# 4-POWER.net
KiCad netlist of a schematic drawn in Altium Designer
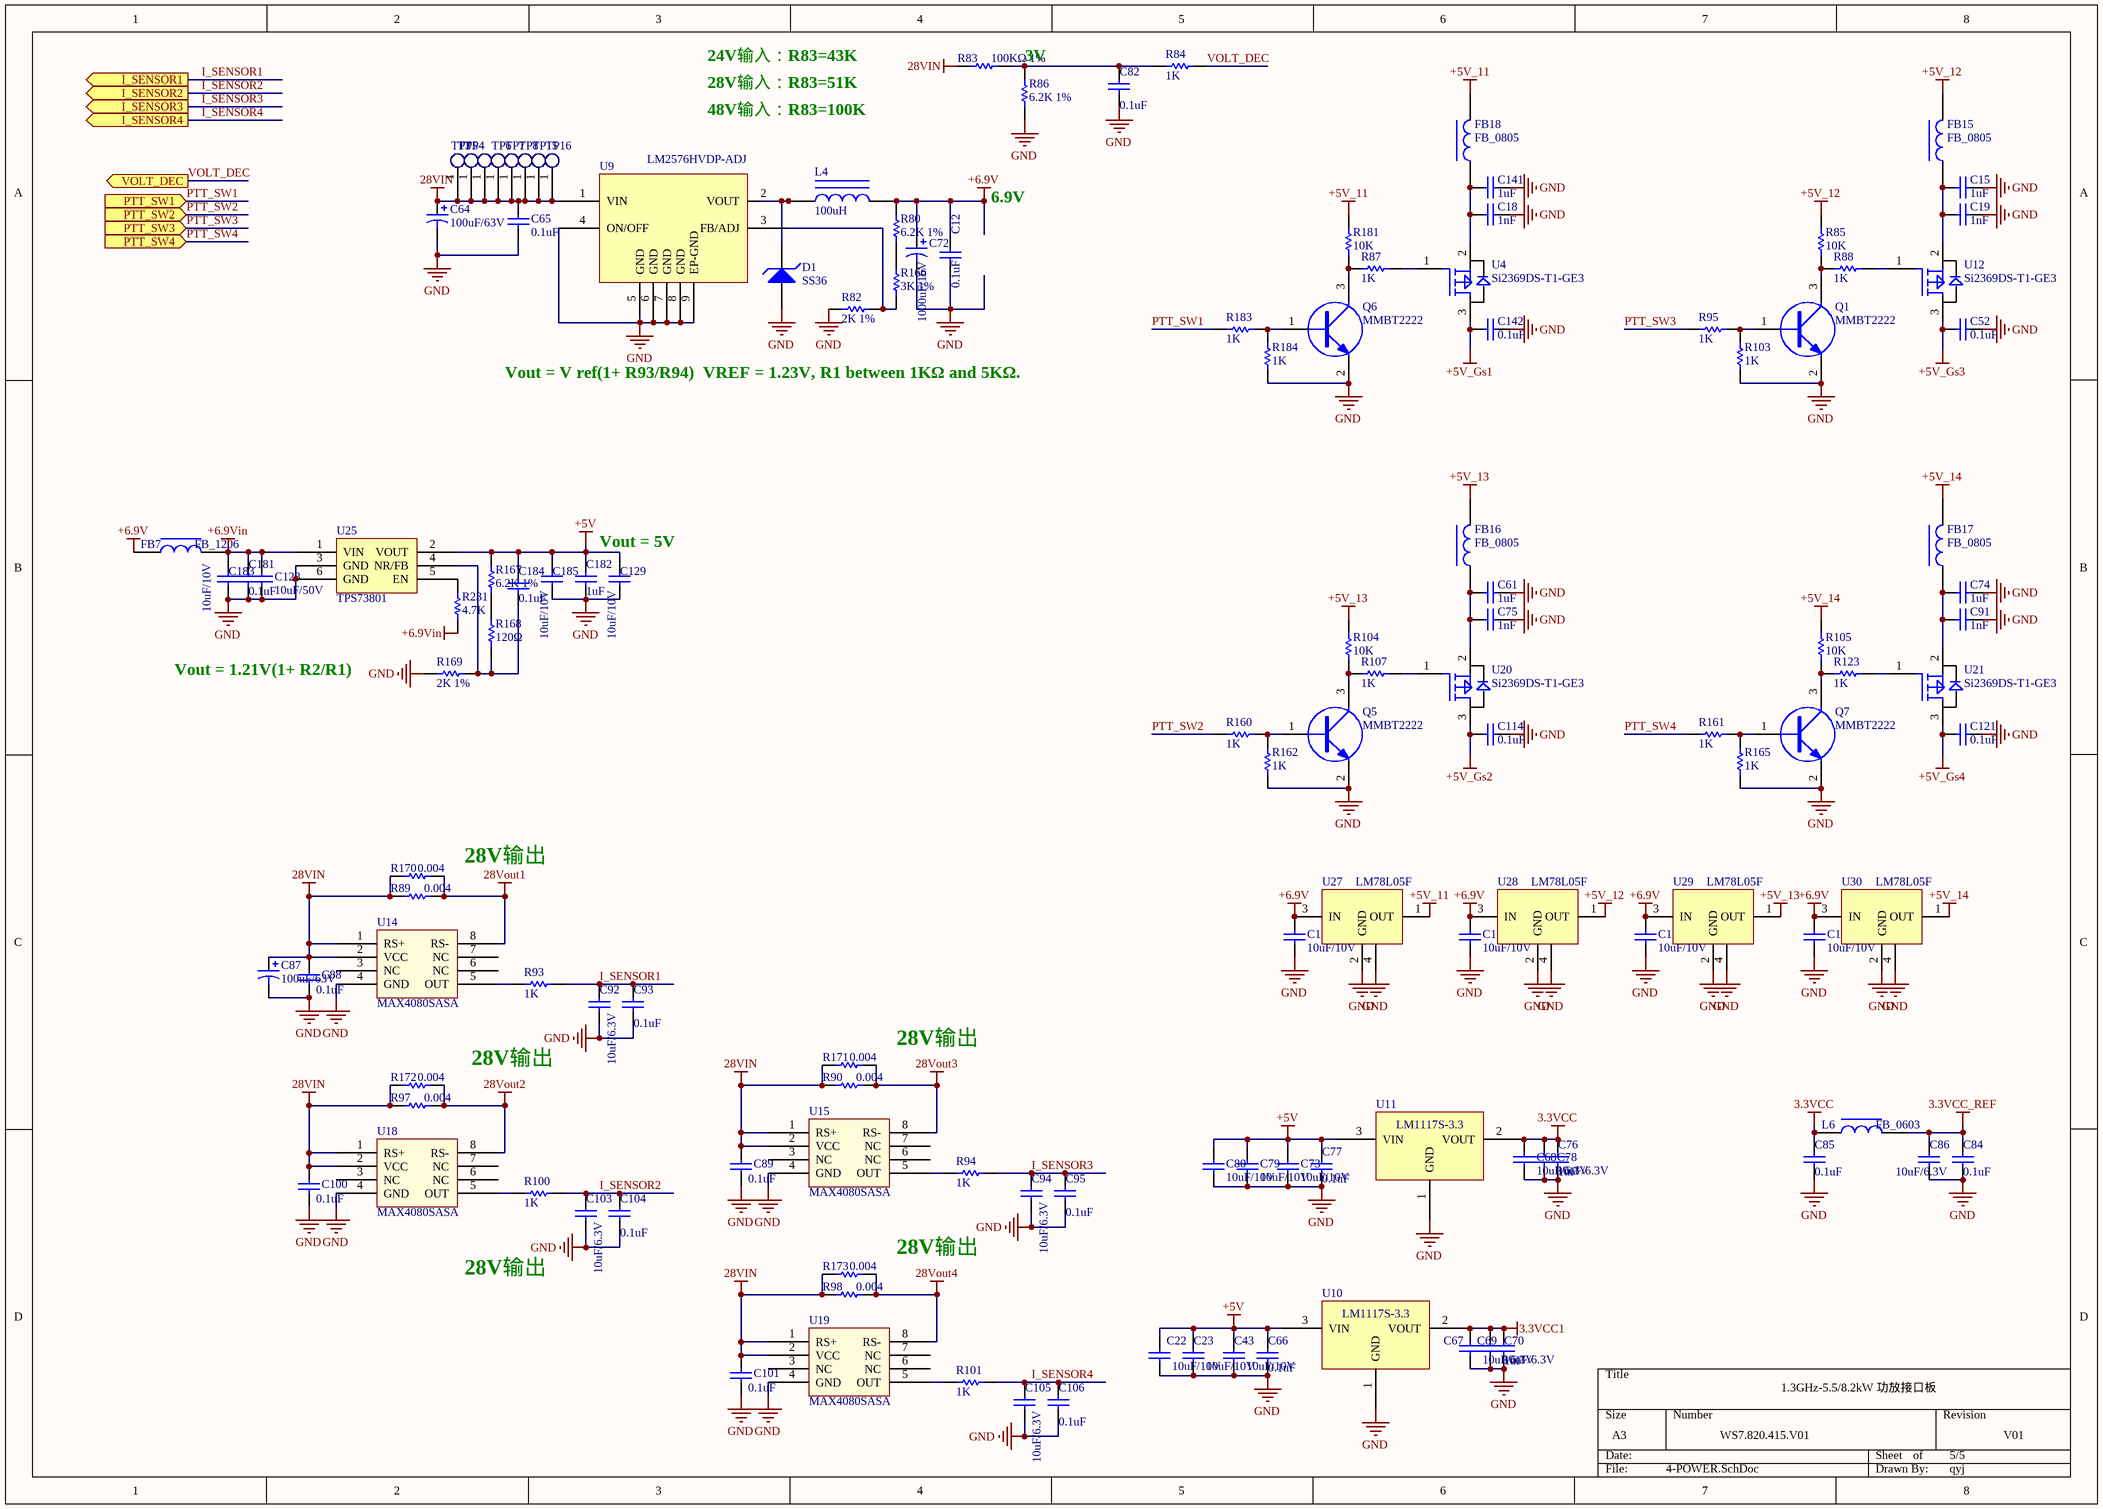
[diagram p0: 4-POWER.SchDoc]

(export (version "E")
  (design (tool "Eeschema 10.0.6"))
  (components
    (comp (ref "C12")
      (value "0.1uF")
      (footprint "C0603")
      (description "贴片电容_GRM188R71H104KA01D_0.1uF±10%,50V,0603")
      (libsource (lib "20贴片电容0603") (part "0.1uF贴片电容"))
    )
    (comp (ref "C15")
      (value "1uF")
      (footprint "C0603")
      (description "贴片电容_GRM188R61A105KA61D_1uF±10%,10V,0603")
      (libsource (lib "20贴片电容0603") (part "1uF贴片电容"))
    )
    (comp (ref "C18")
      (value "1nF")
      (footprint "C0603")
      (description "贴片电容_GRM188R71H102KA01_1000pF±10%,50V,0603")
      (libsource (lib "20贴片电容0603") (part "1000pF贴片电容"))
    )
    (comp (ref "C19")
      (value "1nF")
      (footprint "C0603")
      (description "贴片电容_GRM188R71H102KA01_1000pF±10%,50V,0603")
      (libsource (lib "20贴片电容0603") (part "1000pF贴片电容"))
    )
    (comp (ref "C22")
      (value "10uF/10V")
      (footprint "C0805")
      (description "贴片电容_GRM21BR61A106KE19L_10uF±10%,10V,0805")
      (libsource (lib "21贴片电容0805") (part "10uF贴片电容"))
    )
    (comp (ref "C23")
      (value "10uF/10V")
      (footprint "C0805")
      (description "贴片电容_GRM21BR61A106KE19L_10uF±10%,10V,0805")
      (libsource (lib "21贴片电容0805") (part "10uF贴片电容"))
    )
    (comp (ref "C43")
      (value "10uF/10V")
      (footprint "C0805")
      (description "贴片电容_GRM21BR61A106KE19L_10uF±10%,10V,0805")
      (libsource (lib "21贴片电容0805") (part "10uF贴片电容"))
    )
    (comp (ref "C52")
      (value "0.1uF")
      (footprint "C0603")
      (description "贴片电容_GRM188R71H104KA01D_0.1uF±10%,50V,0603")
      (libsource (lib "20贴片电容0603") (part "0.1uF贴片电容"))
    )
    (comp (ref "C61")
      (value "1uF")
      (footprint "C0603")
      (description "贴片电容_GRM188R61A105KA61D_1uF±10%,10V,0603")
      (libsource (lib "20贴片电容0603") (part "1uF贴片电容"))
    )
    (comp (ref "C64")
      (value "100uF/63V")
      (footprint "ECAP2SM_10R4x10R4")
      (description "贴片电解电容_VEJ101M1JTR-1010_100uF/63V,±20%,表贴D10*H10")
      (libsource (lib "24电解电容") (part "100uF/63V"))
    )
    (comp (ref "C65")
      (value "0.1uF")
      (footprint "C0603")
      (description "贴片电容_GRM188R71H104KA01D_0.1uF±10%,50V,0603")
      (libsource (lib "20贴片电容0603") (part "0.1uF贴片电容"))
    )
    (comp (ref "C66")
      (value "0.1uF")
      (footprint "C0603")
      (description "贴片电容_GRM188R71H104KA01D_0.1uF±10%,50V,0603")
      (libsource (lib "20贴片电容0603") (part "0.1uF贴片电容"))
    )
    (comp (ref "C67")
      (value "10uF/6.3V")
      (footprint "C0603")
      (description "贴片电容_GRM188R60J106ME47D_10uF±20%,6.3V,0603")
      (libsource (lib "20贴片电容0603") (part "10uF贴片电容"))
    )
    (comp (ref "C68")
      (value "10uF/6.3V")
      (footprint "C0603")
      (description "贴片电容_GRM188R60J106ME47D_10uF±20%,6.3V,0603")
      (libsource (lib "20贴片电容0603") (part "10uF贴片电容"))
    )
    (comp (ref "C69")
      (value "10uF/6.3V")
      (footprint "C0603")
      (description "贴片电容_GRM188R60J106ME47D_10uF±20%,6.3V,0603")
      (libsource (lib "20贴片电容0603") (part "10uF贴片电容"))
    )
    (comp (ref "C70")
      (value "1uF")
      (footprint "C0603")
      (description "贴片电容_GRM188R61A105KA61D_1uF±10%,10V,0603")
      (libsource (lib "20贴片电容0603") (part "1uF贴片电容"))
    )
    (comp (ref "C72")
      (value "1000uF/16V")
      (footprint "ECAP2SM_10R4x10R4")
      (description "贴片电解电容_VE102M1CTR-1010_1000uF/16V,±20%,表贴10*10")
      (libsource (lib "24电解电容") (part "1000uF/16V"))
    )
    (comp (ref "C73")
      (value "10uF/10V")
      (footprint "C0805")
      (description "贴片电容_GRM21BR61A106KE19L_10uF±10%,10V,0805")
      (libsource (lib "21贴片电容0805") (part "10uF贴片电容"))
    )
    (comp (ref "C74")
      (value "1uF")
      (footprint "C0603")
      (description "贴片电容_GRM188R61A105KA61D_1uF±10%,10V,0603")
      (libsource (lib "20贴片电容0603") (part "1uF贴片电容"))
    )
    (comp (ref "C75")
      (value "1nF")
      (footprint "C0603")
      (description "贴片电容_GRM188R71H102KA01_1000pF±10%,50V,0603")
      (libsource (lib "20贴片电容0603") (part "1000pF贴片电容"))
    )
    (comp (ref "C76")
      (value "1uF")
      (footprint "C0603")
      (description "贴片电容_GRM188R61A105KA61D_1uF±10%,10V,0603")
      (libsource (lib "20贴片电容0603") (part "1uF贴片电容"))
    )
    (comp (ref "C77")
      (value "0.1uF")
      (footprint "C0603")
      (description "贴片电容_GRM188R71H104KA01D_0.1uF±10%,50V,0603")
      (libsource (lib "20贴片电容0603") (part "0.1uF贴片电容"))
    )
    (comp (ref "C78")
      (value "10uF/6.3V")
      (footprint "C0603")
      (description "贴片电容_GRM188R60J106ME47D_10uF±20%,6.3V,0603")
      (libsource (lib "20贴片电容0603") (part "10uF贴片电容"))
    )
    (comp (ref "C79")
      (value "10uF/10V")
      (footprint "C0805")
      (description "贴片电容_GRM21BR61A106KE19L_10uF±10%,10V,0805")
      (libsource (lib "21贴片电容0805") (part "10uF贴片电容"))
    )
    (comp (ref "C80")
      (value "10uF/10V")
      (footprint "C0805")
      (description "贴片电容_GRM21BR61A106KE19L_10uF±10%,10V,0805")
      (libsource (lib "21贴片电容0805") (part "10uF贴片电容"))
    )
    (comp (ref "C82")
      (value "0.1uF")
      (footprint "C0603")
      (description "贴片电容_GRM188R71H104KA01D_0.1uF±10%,50V,0603")
      (libsource (lib "20贴片电容0603") (part "0.1uF贴片电容"))
    )
    (comp (ref "C84")
      (value "0.1uF")
      (footprint "C0603")
      (description "贴片电容_GRM188R71H104KA01D_0.1uF±10%,50V,0603")
      (libsource (lib "20贴片电容0603") (part "0.1uF贴片电容"))
    )
    (comp (ref "C85")
      (value "0.1uF")
      (footprint "C0603")
      (description "贴片电容_GRM188R71H104KA01D_0.1uF±10%,50V,0603")
      (libsource (lib "20贴片电容0603") (part "0.1uF贴片电容"))
    )
    (comp (ref "C86")
      (value "10uF/6.3V")
      (footprint "C0603")
      (description "贴片电容_GRM188R60J106ME47D_10uF±20%,6.3V,0603")
      (libsource (lib "20贴片电容0603") (part "10uF贴片电容"))
    )
    (comp (ref "C87")
      (value "100uF/63V")
      (footprint "ECAP2SM_10R4x10R4")
      (description "贴片电解电容_VEJ101M1JTR-1010_100uF/63V,±20%,表贴D10*H10")
      (libsource (lib "24电解电容") (part "100uF/63V"))
    )
    (comp (ref "C88")
      (value "0.1uF")
      (footprint "C0603")
      (description "贴片电容_GRM188R71H104KA01D_0.1uF±10%,50V,0603")
      (libsource (lib "20贴片电容0603") (part "0.1uF贴片电容"))
    )
    (comp (ref "C89")
      (value "0.1uF")
      (footprint "C0603")
      (description "贴片电容_GRM188R71H104KA01D_0.1uF±10%,50V,0603")
      (libsource (lib "20贴片电容0603") (part "0.1uF贴片电容"))
    )
    (comp (ref "C91")
      (value "1nF")
      (footprint "C0603")
      (description "贴片电容_GRM188R71H102KA01_1000pF±10%,50V,0603")
      (libsource (lib "20贴片电容0603") (part "1000pF贴片电容"))
    )
    (comp (ref "C92")
      (value "10uF/6.3V")
      (footprint "C0603")
      (description "贴片电容_GRM188R60J106ME47D_10uF±20%,6.3V,0603")
      (libsource (lib "20贴片电容0603") (part "10uF贴片电容"))
    )
    (comp (ref "C93")
      (value "0.1uF")
      (footprint "C0603")
      (description "贴片电容_GRM188R71H104KA01D_0.1uF±10%,50V,0603")
      (libsource (lib "20贴片电容0603") (part "0.1uF贴片电容"))
    )
    (comp (ref "C94")
      (value "10uF/6.3V")
      (footprint "C0603")
      (description "贴片电容_GRM188R60J106ME47D_10uF±20%,6.3V,0603")
      (libsource (lib "20贴片电容0603") (part "10uF贴片电容"))
    )
    (comp (ref "C95")
      (value "0.1uF")
      (footprint "C0603")
      (description "贴片电容_GRM188R71H104KA01D_0.1uF±10%,50V,0603")
      (libsource (lib "20贴片电容0603") (part "0.1uF贴片电容"))
    )
    (comp (ref "C100")
      (value "0.1uF")
      (footprint "C0603")
      (description "贴片电容_GRM188R71H104KA01D_0.1uF±10%,50V,0603")
      (libsource (lib "20贴片电容0603") (part "0.1uF贴片电容"))
    )
    (comp (ref "C101")
      (value "0.1uF")
      (footprint "C0603")
      (description "贴片电容_GRM188R71H104KA01D_0.1uF±10%,50V,0603")
      (libsource (lib "20贴片电容0603") (part "0.1uF贴片电容"))
    )
    (comp (ref "C103")
      (value "10uF/6.3V")
      (footprint "C0603")
      (description "贴片电容_GRM188R60J106ME47D_10uF±20%,6.3V,0603")
      (libsource (lib "20贴片电容0603") (part "10uF贴片电容"))
    )
    (comp (ref "C104")
      (value "0.1uF")
      (footprint "C0603")
      (description "贴片电容_GRM188R71H104KA01D_0.1uF±10%,50V,0603")
      (libsource (lib "20贴片电容0603") (part "0.1uF贴片电容"))
    )
    (comp (ref "C105")
      (value "10uF/6.3V")
      (footprint "C0603")
      (description "贴片电容_GRM188R60J106ME47D_10uF±20%,6.3V,0603")
      (libsource (lib "20贴片电容0603") (part "10uF贴片电容"))
    )
    (comp (ref "C106")
      (value "0.1uF")
      (footprint "C0603")
      (description "贴片电容_GRM188R71H104KA01D_0.1uF±10%,50V,0603")
      (libsource (lib "20贴片电容0603") (part "0.1uF贴片电容"))
    )
    (comp (ref "C114")
      (value "0.1uF")
      (footprint "C0603")
      (description "贴片电容_GRM188R71H104KA01D_0.1uF±10%,50V,0603")
      (libsource (lib "20贴片电容0603") (part "0.1uF贴片电容"))
    )
    (comp (ref "C121")
      (value "0.1uF")
      (footprint "C0603")
      (description "贴片电容_GRM188R71H104KA01D_0.1uF±10%,50V,0603")
      (libsource (lib "20贴片电容0603") (part "0.1uF贴片电容"))
    )
    (comp (ref "C128")
      (value "10uF/50V")
      (footprint "C1210")
      (description "贴片电容_GRM32ER71H106KA12L_10uF±10%,50V,1210")
      (libsource (lib "23贴片电容1210") (part "10uF贴片电容"))
    )
    (comp (ref "C129")
      (value "10uF/10V")
      (footprint "C0805")
      (description "贴片电容_GRM21BR61A106KE19L_10uF±10%,10V,0805")
      (libsource (lib "21贴片电容0805") (part "10uF贴片电容"))
    )
    (comp (ref "C132")
      (value "10uF/10V")
      (footprint "C0805")
      (description "贴片电容_GRM21BR61A106KE19L_10uF±10%,10V,0805")
      (libsource (lib "21贴片电容0805") (part "10uF贴片电容"))
    )
    (comp (ref "C133")
      (value "10uF/10V")
      (footprint "C0805")
      (description "贴片电容_GRM21BR61A106KE19L_10uF±10%,10V,0805")
      (libsource (lib "21贴片电容0805") (part "10uF贴片电容"))
    )
    (comp (ref "C134")
      (value "10uF/10V")
      (footprint "C0805")
      (description "贴片电容_GRM21BR61A106KE19L_10uF±10%,10V,0805")
      (libsource (lib "21贴片电容0805") (part "10uF贴片电容"))
    )
    (comp (ref "C135")
      (value "10uF/10V")
      (footprint "C0805")
      (description "贴片电容_GRM21BR61A106KE19L_10uF±10%,10V,0805")
      (libsource (lib "21贴片电容0805") (part "10uF贴片电容"))
    )
    (comp (ref "C141")
      (value "1uF")
      (footprint "C0603")
      (description "贴片电容_GRM188R61A105KA61D_1uF±10%,10V,0603")
      (libsource (lib "20贴片电容0603") (part "1uF贴片电容"))
    )
    (comp (ref "C142")
      (value "0.1uF")
      (footprint "C0603")
      (description "贴片电容_GRM188R71H104KA01D_0.1uF±10%,50V,0603")
      (libsource (lib "20贴片电容0603") (part "0.1uF贴片电容"))
    )
    (comp (ref "C181")
      (value "0.1uF")
      (footprint "C0603")
      (description "贴片电容_GRM188R71H104KA01D_0.1uF±10%,50V,0603")
      (libsource (lib "20贴片电容0603") (part "0.1uF贴片电容"))
    )
    (comp (ref "C182")
      (value "1uF")
      (footprint "C0603")
      (description "贴片电容_GRM188R61A105KA61D_1uF±10%,10V,0603")
      (libsource (lib "20贴片电容0603") (part "1uF贴片电容"))
    )
    (comp (ref "C183")
      (value "10uF/10V")
      (footprint "C0805")
      (description "贴片电容_GRM21BR61A106KE19L_10uF±10%,10V,0805")
      (libsource (lib "21贴片电容0805") (part "10uF贴片电容"))
    )
    (comp (ref "C184")
      (value "0.1uF")
      (footprint "C0603")
      (description "贴片电容_GRM188R71H104KA01D_0.1uF±10%,50V,0603")
      (libsource (lib "20贴片电容0603") (part "0.1uF贴片电容"))
    )
    (comp (ref "C185")
      (value "10uF/10V")
      (footprint "C0805")
      (description "贴片电容_GRM21BR61A106KE19L_10uF±10%,10V,0805")
      (libsource (lib "21贴片电容0805") (part "10uF贴片电容"))
    )
    (comp (ref "D1")
      (value "SS36")
      (footprint "DO-214AC")
      (description "肖特基整流二极管_SS36_封装SMA,3A/60V")
      (libsource (lib "40二极管") (part "肖特基整流二极管_SS36"))
    )
    (comp (ref "FB7")
      (value "FB_1206")
      (footprint "L1206")
      (description "贴片磁珠_30R,6A,1206")
      (libsource (lib "34贴片磁珠1206") (part "1206贴片磁珠"))
    )
    (comp (ref "FB15")
      (value "FB_0805")
      (footprint "L0805")
      (description "贴片磁珠_600R,0805")
      (libsource (lib "33贴片磁珠0805") (part "0805贴片磁珠"))
    )
    (comp (ref "FB16")
      (value "FB_0805")
      (footprint "L0805")
      (description "贴片磁珠_600R,0805")
      (libsource (lib "33贴片磁珠0805") (part "0805贴片磁珠"))
    )
    (comp (ref "FB17")
      (value "FB_0805")
      (footprint "L0805")
      (description "贴片磁珠_600R,0805")
      (libsource (lib "33贴片磁珠0805") (part "0805贴片磁珠"))
    )
    (comp (ref "FB18")
      (value "FB_0805")
      (footprint "L0805")
      (description "贴片磁珠_600R,0805")
      (libsource (lib "33贴片磁珠0805") (part "0805贴片磁珠"))
    )
    (comp (ref "L4")
      (value "100uH")
      (footprint "PL2SM-12R5x12R5")
      (description "贴片功率电感_SLF12575T-101M1R9-PF_100uH±20%,额定电流1.9A,12.5x12.5")
      (libsource (lib "32贴片功率电感") (part "100uH贴片功率电感"))
    )
    (comp (ref "L6")
      (value "FB_0603")
      (footprint "L0603")
      (description "贴片磁珠_100R,0603")
      (libsource (lib "32贴片磁珠0603") (part "0603贴片磁珠"))
    )
    (comp (ref "Q1")
      (value "MMBT2222")
      (footprint "SOT23-3")
      (description "NPN三极管_MMBT2222_表贴SOT23")
      (libsource (lib "50三极管") (part "MMBT2222"))
    )
    (comp (ref "Q5")
      (value "MMBT2222")
      (footprint "SOT23-3")
      (description "NPN三极管_MMBT2222_表贴SOT23")
      (libsource (lib "50三极管") (part "MMBT2222"))
    )
    (comp (ref "Q6")
      (value "MMBT2222")
      (footprint "SOT23-3")
      (description "NPN三极管_MMBT2222_表贴SOT23")
      (libsource (lib "50三极管") (part "MMBT2222"))
    )
    (comp (ref "Q7")
      (value "MMBT2222")
      (footprint "SOT23-3")
      (description "NPN三极管_MMBT2222_表贴SOT23")
      (libsource (lib "50三极管") (part "MMBT2222"))
    )
    (comp (ref "R80")
      (value "6.2K 1%")
      (footprint "R0603")
      (description "贴片电阻_6.2K±5%,0603")
      (libsource (lib "10贴片电阻0603") (part "6.2K贴片电阻"))
    )
    (comp (ref "R82")
      (value "2K 1%")
      (footprint "R0603")
      (description "贴片电阻_2K±5%,0603")
      (libsource (lib "10贴片电阻0603") (part "2K贴片电阻"))
    )
    (comp (ref "R83")
      (value "100KΩ 1%")
      (footprint "R0603")
      (description "贴片电阻_12.4K±1%,0603")
      (libsource (lib "10贴片电阻0603") (part "12.4K贴片电阻"))
    )
    (comp (ref "R84")
      (value "1K")
      (footprint "R0603")
      (description "贴片电阻_1K±5%,0603")
      (libsource (lib "10贴片电阻0603") (part "1K贴片电阻"))
    )
    (comp (ref "R85")
      (value "10K")
      (footprint "R0603")
      (description "贴片电阻_10K±5%,0603")
      (libsource (lib "10贴片电阻0603") (part "10K贴片电阻"))
    )
    (comp (ref "R86")
      (value "6.2K 1%")
      (footprint "R0603")
      (description "贴片电阻_1.5K±5%,0603")
      (libsource (lib "10贴片电阻0603") (part "1.5K贴片电阻"))
    )
    (comp (ref "R87")
      (value "1K")
      (footprint "R0603")
      (description "贴片电阻_1K±5%,0603")
      (libsource (lib "10贴片电阻0603") (part "1K贴片电阻"))
    )
    (comp (ref "R88")
      (value "1K")
      (footprint "R0603")
      (description "贴片电阻_1K±5%,0603")
      (libsource (lib "10贴片电阻0603") (part "1K贴片电阻"))
    )
    (comp (ref "R89")
      (value "0.004")
      (footprint "R2512")
      (description "贴片电阻_LR12DTDSR004_0.004±5%,2W,2512")
      (libsource (lib "15贴片检流电阻") (part "0.004Ω检流电阻-标准封装"))
    )
    (comp (ref "R90")
      (value "0.004")
      (footprint "R2512")
      (description "贴片电阻_LR12DTDSR004_0.004±5%,2W,2512")
      (libsource (lib "15贴片检流电阻") (part "0.004Ω检流电阻-标准封装"))
    )
    (comp (ref "R93")
      (value "1K")
      (footprint "R0603")
      (description "贴片电阻_1K±5%,0603")
      (libsource (lib "10贴片电阻0603") (part "1K贴片电阻"))
    )
    (comp (ref "R94")
      (value "1K")
      (footprint "R0603")
      (description "贴片电阻_1K±5%,0603")
      (libsource (lib "10贴片电阻0603") (part "1K贴片电阻"))
    )
    (comp (ref "R95")
      (value "1K")
      (footprint "R0603")
      (description "贴片电阻_1K±5%,0603")
      (libsource (lib "10贴片电阻0603") (part "1K贴片电阻"))
    )
    (comp (ref "R97")
      (value "0.004")
      (footprint "R2512")
      (description "贴片电阻_LR12DTDSR004_0.004±5%,2W,2512")
      (libsource (lib "15贴片检流电阻") (part "0.004Ω检流电阻-标准封装"))
    )
    (comp (ref "R98")
      (value "0.004")
      (footprint "R2512")
      (description "贴片电阻_LR12DTDSR004_0.004±5%,2W,2512")
      (libsource (lib "15贴片检流电阻") (part "0.004Ω检流电阻-标准封装"))
    )
    (comp (ref "R100")
      (value "1K")
      (footprint "R0603")
      (description "贴片电阻_1K±5%,0603")
      (libsource (lib "10贴片电阻0603") (part "1K贴片电阻"))
    )
    (comp (ref "R101")
      (value "1K")
      (footprint "R0603")
      (description "贴片电阻_1K±5%,0603")
      (libsource (lib "10贴片电阻0603") (part "1K贴片电阻"))
    )
    (comp (ref "R103")
      (value "1K")
      (footprint "R0603")
      (description "贴片电阻_1K±5%,0603")
      (libsource (lib "10贴片电阻0603") (part "1K贴片电阻"))
    )
    (comp (ref "R104")
      (value "10K")
      (footprint "R0603")
      (description "贴片电阻_10K±5%,0603")
      (libsource (lib "10贴片电阻0603") (part "10K贴片电阻"))
    )
    (comp (ref "R105")
      (value "10K")
      (footprint "R0603")
      (description "贴片电阻_10K±5%,0603")
      (libsource (lib "10贴片电阻0603") (part "10K贴片电阻"))
    )
    (comp (ref "R107")
      (value "1K")
      (footprint "R0603")
      (description "贴片电阻_1K±5%,0603")
      (libsource (lib "10贴片电阻0603") (part "1K贴片电阻"))
    )
    (comp (ref "R123")
      (value "1K")
      (footprint "R0603")
      (description "贴片电阻_1K±5%,0603")
      (libsource (lib "10贴片电阻0603") (part "1K贴片电阻"))
    )
    (comp (ref "R160")
      (value "1K")
      (footprint "R0603")
      (description "贴片电阻_1K±5%,0603")
      (libsource (lib "10贴片电阻0603") (part "1K贴片电阻"))
    )
    (comp (ref "R161")
      (value "1K")
      (footprint "R0603")
      (description "贴片电阻_1K±5%,0603")
      (libsource (lib "10贴片电阻0603") (part "1K贴片电阻"))
    )
    (comp (ref "R162")
      (value "1K")
      (footprint "R0603")
      (description "贴片电阻_1K±5%,0603")
      (libsource (lib "10贴片电阻0603") (part "1K贴片电阻"))
    )
    (comp (ref "R165")
      (value "1K")
      (footprint "R0603")
      (description "贴片电阻_1K±5%,0603")
      (libsource (lib "10贴片电阻0603") (part "1K贴片电阻"))
    )
    (comp (ref "R166")
      (value "3K 1%")
      (footprint "R0603")
      (description "贴片电阻_3K±5%,0603")
      (libsource (lib "10贴片电阻0603") (part "3K贴片电阻"))
    )
    (comp (ref "R167")
      (value "6.2K 1%")
      (footprint "R0603")
      (description "贴片电阻_6.2K±5%,0603")
      (libsource (lib "10贴片电阻0603") (part "6.2K贴片电阻"))
    )
    (comp (ref "R168")
      (value "120Ω")
      (footprint "R0603")
      (description "贴片电阻_120Ω±5%,0603")
      (libsource (lib "10贴片电阻0603") (part "120Ω贴片电阻"))
    )
    (comp (ref "R169")
      (value "2K 1%")
      (footprint "R0603")
      (description "贴片电阻_2K±5%,0603")
      (libsource (lib "10贴片电阻0603") (part "2K贴片电阻"))
    )
    (comp (ref "R170")
      (value "0.004")
      (footprint "R2512")
      (description "贴片电阻_LR12DTDSR004_0.004±5%,2W,2512")
      (libsource (lib "15贴片检流电阻") (part "0.004Ω检流电阻-标准封装"))
    )
    (comp (ref "R171")
      (value "0.004")
      (footprint "R2512")
      (description "贴片电阻_LR12DTDSR004_0.004±5%,2W,2512")
      (libsource (lib "15贴片检流电阻") (part "0.004Ω检流电阻-标准封装"))
    )
    (comp (ref "R172")
      (value "0.004")
      (footprint "R2512")
      (description "贴片电阻_LR12DTDSR004_0.004±5%,2W,2512")
      (libsource (lib "15贴片检流电阻") (part "0.004Ω检流电阻-标准封装"))
    )
    (comp (ref "R173")
      (value "0.004")
      (footprint "R2512")
      (description "贴片电阻_LR12DTDSR004_0.004±5%,2W,2512")
      (libsource (lib "15贴片检流电阻") (part "0.004Ω检流电阻-标准封装"))
    )
    (comp (ref "R181")
      (value "10K")
      (footprint "R0603")
      (description "贴片电阻_10K±5%,0603")
      (libsource (lib "10贴片电阻0603") (part "10K贴片电阻"))
    )
    (comp (ref "R183")
      (value "1K")
      (footprint "R0603")
      (description "贴片电阻_1K±5%,0603")
      (libsource (lib "10贴片电阻0603") (part "1K贴片电阻"))
    )
    (comp (ref "R184")
      (value "1K")
      (footprint "R0603")
      (description "贴片电阻_1K±5%,0603")
      (libsource (lib "10贴片电阻0603") (part "1K贴片电阻"))
    )
    (comp (ref "R231")
      (value "4.7K")
      (footprint "R0603")
      (description "贴片电阻_4.7K±5%,0603")
      (libsource (lib "10贴片电阻0603") (part "4.7K贴片电阻"))
    )
    (comp (ref "TP3")
      (value "RTF-76-006-M4-S")
      (footprint "FC-M4")
      (description "表贴测试点1mm")
      (libsource (lib "92-其他（穿心电容，test等）") (part "TP2mm"))
    )
    (comp (ref "TP4")
      (value "RTF-76-006-M4-S")
      (footprint "FC-M4")
      (description "表贴测试点1mm")
      (libsource (lib "92-其他（穿心电容，test等）") (part "TP2mm"))
    )
    (comp (ref "TP5")
      (value "RTF-76-006-M4-S")
      (footprint "FC-M4")
      (description "表贴测试点1mm")
      (libsource (lib "92-其他（穿心电容，test等）") (part "TP2mm"))
    )
    (comp (ref "TP6")
      (value "RTF-76-006-M4-S")
      (footprint "FC-M4")
      (description "表贴测试点1mm")
      (libsource (lib "92-其他（穿心电容，test等）") (part "TP2mm"))
    )
    (comp (ref "TP7")
      (value "RTF-76-006-M4-S")
      (footprint "FC-M4")
      (description "表贴测试点1mm")
      (libsource (lib "92-其他（穿心电容，test等）") (part "TP2mm"))
    )
    (comp (ref "TP8")
      (value "RTF-76-006-M4-S")
      (footprint "FC-M4")
      (description "表贴测试点1mm")
      (libsource (lib "92-其他（穿心电容，test等）") (part "TP2mm"))
    )
    (comp (ref "TP15")
      (value "RTF-76-006-M4-S")
      (footprint "FC-M4")
      (description "表贴测试点1mm")
      (libsource (lib "92-其他（穿心电容，test等）") (part "TP2mm"))
    )
    (comp (ref "TP16")
      (value "RTF-76-006-M4-S")
      (footprint "FC-M4")
      (description "表贴测试点1mm")
      (libsource (lib "92-其他（穿心电容，test等）") (part "TP2mm"))
    )
    (comp (ref "U4")
      (value "Si2369DS-T1-GE3")
      (footprint "SOT23-3")
      (description "P-MOS_Si2369DS-T1-GE3_SOT23")
      (libsource (lib "51场效应管") (part "Si2369DS-T1-GE3"))
    )
    (comp (ref "U9")
      (value "LM2576HVDP-ADJ")
      (footprint "SOIC8_1R27_3R9x4R9-1")
      (description "稳压集成电路_LM2576HVDP-ADJ_3A输出,SOIC8")
      (libsource (lib "78电源芯片") (part "LM2576HVDP-ADJ"))
    )
    (comp (ref "U10")
      (value "LM1117S-3.3")
      (footprint "SOT-223")
      (description "LDO_LM1117S-3.3_1A输出,SOT223")
      (libsource (lib "78电源芯片") (part "LM1117S-3.3"))
    )
    (comp (ref "U11")
      (value "LM1117S-3.3")
      (footprint "SOT-223")
      (description "LDO_LM1117S-3.3_1A输出,SOT223")
      (libsource (lib "78电源芯片") (part "LM1117S-3.3"))
    )
    (comp (ref "U12")
      (value "Si2369DS-T1-GE3")
      (footprint "SOT23-3")
      (description "P-MOS_Si2369DS-T1-GE3_SOT23")
      (libsource (lib "51场效应管") (part "Si2369DS-T1-GE3"))
    )
    (comp (ref "U14")
      (value "MAX4080SASA")
      (footprint "SOIC8_1R27_3R9x4R9")
      (description "电流检测放大器_MAX4080SASA_SOIC8")
      (libsource (lib "79电流检测芯片") (part "MAX4080TASA"))
    )
    (comp (ref "U15")
      (value "MAX4080SASA")
      (footprint "SOIC8_1R27_3R9x4R9")
      (description "电流检测放大器_MAX4080SASA_SOIC8")
      (libsource (lib "79电流检测芯片") (part "MAX4080TASA"))
    )
    (comp (ref "U18")
      (value "MAX4080SASA")
      (footprint "SOIC8_1R27_3R9x4R9")
      (description "电流检测放大器_MAX4080SASA_SOIC8")
      (libsource (lib "79电流检测芯片") (part "MAX4080TASA"))
    )
    (comp (ref "U19")
      (value "MAX4080SASA")
      (footprint "SOIC8_1R27_3R9x4R9")
      (description "电流检测放大器_MAX4080SASA_SOIC8")
      (libsource (lib "79电流检测芯片") (part "MAX4080TASA"))
    )
    (comp (ref "U20")
      (value "Si2369DS-T1-GE3")
      (footprint "SOT23-3")
      (description "P-MOS_Si2369DS-T1-GE3_SOT23")
      (libsource (lib "51场效应管") (part "Si2369DS-T1-GE3"))
    )
    (comp (ref "U21")
      (value "Si2369DS-T1-GE3")
      (footprint "SOT23-3")
      (description "P-MOS_Si2369DS-T1-GE3_SOT23")
      (libsource (lib "51场效应管") (part "Si2369DS-T1-GE3"))
    )
    (comp (ref "U25")
      (value "TPS73801")
      (footprint "SOT-223-6")
      (description "LDO_TPS73801_1A输出,SOT223-6")
      (libsource (lib "78电源芯片") (part "TPS73701DCQ"))
    )
    (comp (ref "U27")
      (value "LM78L05F")
      (footprint "SOT-89")
      (description "功率放大器_LM78L05F_5V输出,100mA输出,SOT89")
      (libsource (lib "78电源芯片") (part "LM78L05F"))
    )
    (comp (ref "U28")
      (value "LM78L05F")
      (footprint "SOT-89")
      (description "功率放大器_LM78L05F_5V输出,100mA输出,SOT89")
      (libsource (lib "78电源芯片") (part "LM78L05F"))
    )
    (comp (ref "U29")
      (value "LM78L05F")
      (footprint "SOT-89")
      (description "功率放大器_LM78L05F_5V输出,100mA输出,SOT89")
      (libsource (lib "78电源芯片") (part "LM78L05F"))
    )
    (comp (ref "U30")
      (value "LM78L05F")
      (footprint "SOT-89")
      (description "功率放大器_LM78L05F_5V输出,100mA输出,SOT89")
      (libsource (lib "78电源芯片") (part "LM78L05F"))
    )
  )
  (nets
    (net (code "1") (name "+5V") (class "Default")
      (node (ref "C129") (pin "2") (pinfunction "2_2") (pintype "passive"))
      (node (ref "C182") (pin "2") (pinfunction "2_2") (pintype "passive"))
      (node (ref "C184") (pin "2") (pinfunction "2_2") (pintype "passive"))
      (node (ref "C185") (pin "2") (pinfunction "2_2") (pintype "passive"))
      (node (ref "C22") (pin "2") (pinfunction "2_2") (pintype "passive"))
      (node (ref "C23") (pin "2") (pinfunction "2_2") (pintype "passive"))
      (node (ref "C43") (pin "2") (pinfunction "2_2") (pintype "passive"))
      (node (ref "C66") (pin "2") (pinfunction "2_2") (pintype "passive"))
      (node (ref "C73") (pin "2") (pinfunction "2_2") (pintype "passive"))
      (node (ref "C77") (pin "2") (pinfunction "2_2") (pintype "passive"))
      (node (ref "C79") (pin "2") (pinfunction "2_2") (pintype "passive"))
      (node (ref "C80") (pin "2") (pinfunction "2_2") (pintype "passive"))
      (node (ref "R167") (pin "2") (pinfunction "2_2") (pintype "passive"))
      (node (ref "U10") (pin "3") (pinfunction "VIN_3") (pintype "passive"))
      (node (ref "U11") (pin "3") (pinfunction "VIN_3") (pintype "passive"))
      (node (ref "U25") (pin "2") (pinfunction "VOUT_2") (pintype "passive"))
    )
    (net (code "2") (name "+5V_11") (class "Default")
      (node (ref "FB18") (pin "2") (pinfunction "2_2") (pintype "passive"))
      (node (ref "R181") (pin "2") (pinfunction "2_2") (pintype "passive"))
      (node (ref "U27") (pin "1") (pinfunction "OUT_1") (pintype "passive"))
    )
    (net (code "3") (name "+5V_12") (class "Default")
      (node (ref "FB15") (pin "2") (pinfunction "2_2") (pintype "passive"))
      (node (ref "R85") (pin "2") (pinfunction "2_2") (pintype "passive"))
      (node (ref "U28") (pin "1") (pinfunction "OUT_1") (pintype "passive"))
    )
    (net (code "4") (name "+5V_13") (class "Default")
      (node (ref "FB16") (pin "2") (pinfunction "2_2") (pintype "passive"))
      (node (ref "R104") (pin "2") (pinfunction "2_2") (pintype "passive"))
      (node (ref "U29") (pin "1") (pinfunction "OUT_1") (pintype "passive"))
    )
    (net (code "5") (name "+5V_14") (class "Default")
      (node (ref "FB17") (pin "2") (pinfunction "2_2") (pintype "passive"))
      (node (ref "R105") (pin "2") (pinfunction "2_2") (pintype "passive"))
      (node (ref "U30") (pin "1") (pinfunction "OUT_1") (pintype "passive"))
    )
    (net (code "6") (name "+5V_Gs1") (class "Default")
      (node (ref "C142") (pin "2") (pinfunction "2_2") (pintype "passive"))
      (node (ref "U4") (pin "3") (pinfunction "D_3") (pintype "passive"))
    )
    (net (code "7") (name "+5V_Gs2") (class "Default")
      (node (ref "C114") (pin "2") (pinfunction "2_2") (pintype "passive"))
      (node (ref "U20") (pin "3") (pinfunction "D_3") (pintype "passive"))
    )
    (net (code "8") (name "+5V_Gs3") (class "Default")
      (node (ref "C52") (pin "2") (pinfunction "2_2") (pintype "passive"))
      (node (ref "U12") (pin "3") (pinfunction "D_3") (pintype "passive"))
    )
    (net (code "9") (name "+5V_Gs4") (class "Default")
      (node (ref "C121") (pin "2") (pinfunction "2_2") (pintype "passive"))
      (node (ref "U21") (pin "3") (pinfunction "D_3") (pintype "passive"))
    )
    (net (code "10") (name "+6.9V") (class "Default")
      (node (ref "C12") (pin "2") (pinfunction "2_2") (pintype "passive"))
      (node (ref "C132") (pin "2") (pinfunction "2_2") (pintype "passive"))
      (node (ref "C133") (pin "2") (pinfunction "2_2") (pintype "passive"))
      (node (ref "C134") (pin "2") (pinfunction "2_2") (pintype "passive"))
      (node (ref "C135") (pin "2") (pinfunction "2_2") (pintype "passive"))
      (node (ref "C72") (pin "1") (pinfunction "1_1") (pintype "passive"))
      (node (ref "FB7") (pin "1") (pinfunction "1_1") (pintype "passive"))
      (node (ref "L4") (pin "2") (pinfunction "2_2") (pintype "passive"))
      (node (ref "R80") (pin "2") (pinfunction "2_2") (pintype "passive"))
      (node (ref "U27") (pin "3") (pinfunction "IN_3") (pintype "passive"))
      (node (ref "U28") (pin "3") (pinfunction "IN_3") (pintype "passive"))
      (node (ref "U29") (pin "3") (pinfunction "IN_3") (pintype "passive"))
      (node (ref "U30") (pin "3") (pinfunction "IN_3") (pintype "passive"))
    )
    (net (code "11") (name "+6.9Vin") (class "Default")
      (node (ref "C128") (pin "2") (pinfunction "2_2") (pintype "passive"))
      (node (ref "C181") (pin "2") (pinfunction "2_2") (pintype "passive"))
      (node (ref "C183") (pin "2") (pinfunction "2_2") (pintype "passive"))
      (node (ref "FB7") (pin "2") (pinfunction "2_2") (pintype "passive"))
      (node (ref "R231") (pin "2") (pinfunction "2_2") (pintype "passive"))
      (node (ref "U25") (pin "1") (pinfunction "VIN_1") (pintype "passive"))
    )
    (net (code "12") (name "/I_SENSOR1") (class "Default")
      (node (ref "C92") (pin "2") (pinfunction "2_2") (pintype "passive"))
      (node (ref "C93") (pin "2") (pinfunction "2_2") (pintype "passive"))
      (node (ref "R93") (pin "2") (pinfunction "2_2") (pintype "passive"))
    )
    (net (code "13") (name "/I_SENSOR2") (class "Default")
      (node (ref "C103") (pin "2") (pinfunction "2_2") (pintype "passive"))
      (node (ref "C104") (pin "2") (pinfunction "2_2") (pintype "passive"))
      (node (ref "R100") (pin "2") (pinfunction "2_2") (pintype "passive"))
    )
    (net (code "14") (name "/I_SENSOR3") (class "Default")
      (node (ref "C94") (pin "2") (pinfunction "2_2") (pintype "passive"))
      (node (ref "C95") (pin "2") (pinfunction "2_2") (pintype "passive"))
      (node (ref "R94") (pin "2") (pinfunction "2_2") (pintype "passive"))
    )
    (net (code "15") (name "/I_SENSOR4") (class "Default")
      (node (ref "C105") (pin "2") (pinfunction "2_2") (pintype "passive"))
      (node (ref "C106") (pin "2") (pinfunction "2_2") (pintype "passive"))
      (node (ref "R101") (pin "2") (pinfunction "2_2") (pintype "passive"))
    )
    (net (code "16") (name "/PTT_SW1") (class "Default")
      (node (ref "R183") (pin "1") (pinfunction "1_1") (pintype "passive"))
    )
    (net (code "17") (name "/PTT_SW2") (class "Default")
      (node (ref "R160") (pin "1") (pinfunction "1_1") (pintype "passive"))
    )
    (net (code "18") (name "/PTT_SW3") (class "Default")
      (node (ref "R95") (pin "1") (pinfunction "1_1") (pintype "passive"))
    )
    (net (code "19") (name "/PTT_SW4") (class "Default")
      (node (ref "R161") (pin "1") (pinfunction "1_1") (pintype "passive"))
    )
    (net (code "20") (name "/VOLT_DEC") (class "Default")
      (node (ref "R84") (pin "1") (pinfunction "1_1") (pintype "passive"))
    )
    (net (code "21") (name "3.3VCC") (class "Default")
      (node (ref "C68") (pin "2") (pinfunction "2_2") (pintype "passive"))
      (node (ref "C76") (pin "2") (pinfunction "2_2") (pintype "passive"))
      (node (ref "C78") (pin "2") (pinfunction "2_2") (pintype "passive"))
      (node (ref "C85") (pin "2") (pinfunction "2_2") (pintype "passive"))
      (node (ref "L6") (pin "1") (pinfunction "1_1") (pintype "passive"))
      (node (ref "U11") (pin "2") (pinfunction "VOUT_2") (pintype "passive"))
    )
    (net (code "22") (name "3.3VCC1") (class "Default")
      (node (ref "C67") (pin "2") (pinfunction "2_2") (pintype "passive"))
      (node (ref "C69") (pin "2") (pinfunction "2_2") (pintype "passive"))
      (node (ref "C70") (pin "2") (pinfunction "2_2") (pintype "passive"))
      (node (ref "U10") (pin "2") (pinfunction "VOUT_2") (pintype "passive"))
    )
    (net (code "23") (name "3.3VCC_REF") (class "Default")
      (node (ref "C84") (pin "2") (pinfunction "2_2") (pintype "passive"))
      (node (ref "C86") (pin "2") (pinfunction "2_2") (pintype "passive"))
      (node (ref "L6") (pin "2") (pinfunction "2_2") (pintype "passive"))
    )
    (net (code "24") (name "28VIN") (class "Default")
      (node (ref "C100") (pin "2") (pinfunction "2_2") (pintype "passive"))
      (node (ref "C101") (pin "2") (pinfunction "2_2") (pintype "passive"))
      (node (ref "C64") (pin "1") (pinfunction "1_1") (pintype "passive"))
      (node (ref "C65") (pin "2") (pinfunction "2_2") (pintype "passive"))
      (node (ref "C87") (pin "1") (pinfunction "1_1") (pintype "passive"))
      (node (ref "C88") (pin "2") (pinfunction "2_2") (pintype "passive"))
      (node (ref "C89") (pin "2") (pinfunction "2_2") (pintype "passive"))
      (node (ref "R170") (pin "1") (pinfunction "1_1") (pintype "passive"))
      (node (ref "R171") (pin "1") (pinfunction "1_1") (pintype "passive"))
      (node (ref "R172") (pin "1") (pinfunction "1_1") (pintype "passive"))
      (node (ref "R173") (pin "1") (pinfunction "1_1") (pintype "passive"))
      (node (ref "R83") (pin "1") (pinfunction "1_1") (pintype "passive"))
      (node (ref "R89") (pin "1") (pinfunction "1_1") (pintype "passive"))
      (node (ref "R90") (pin "1") (pinfunction "1_1") (pintype "passive"))
      (node (ref "R97") (pin "1") (pinfunction "1_1") (pintype "passive"))
      (node (ref "R98") (pin "1") (pinfunction "1_1") (pintype "passive"))
      (node (ref "TP15") (pin "1") (pinfunction "TP_1") (pintype "passive"))
      (node (ref "TP16") (pin "1") (pinfunction "TP_1") (pintype "passive"))
      (node (ref "TP3") (pin "1") (pinfunction "TP_1") (pintype "passive"))
      (node (ref "TP4") (pin "1") (pinfunction "TP_1") (pintype "passive"))
      (node (ref "TP5") (pin "1") (pinfunction "TP_1") (pintype "passive"))
      (node (ref "TP6") (pin "1") (pinfunction "TP_1") (pintype "passive"))
      (node (ref "TP7") (pin "1") (pinfunction "TP_1") (pintype "passive"))
      (node (ref "TP8") (pin "1") (pinfunction "TP_1") (pintype "passive"))
      (node (ref "U14") (pin "1") (pinfunction "RS+_1") (pintype "passive"))
      (node (ref "U14") (pin "2") (pinfunction "VCC_2") (pintype "passive"))
      (node (ref "U15") (pin "1") (pinfunction "RS+_1") (pintype "passive"))
      (node (ref "U15") (pin "2") (pinfunction "VCC_2") (pintype "passive"))
      (node (ref "U18") (pin "1") (pinfunction "RS+_1") (pintype "passive"))
      (node (ref "U18") (pin "2") (pinfunction "VCC_2") (pintype "passive"))
      (node (ref "U19") (pin "1") (pinfunction "RS+_1") (pintype "passive"))
      (node (ref "U19") (pin "2") (pinfunction "VCC_2") (pintype "passive"))
      (node (ref "U9") (pin "1") (pinfunction "VIN_1") (pintype "passive"))
    )
    (net (code "25") (name "28Vout1") (class "Default")
      (node (ref "R170") (pin "2") (pinfunction "2_2") (pintype "passive"))
      (node (ref "R89") (pin "2") (pinfunction "2_2") (pintype "passive"))
      (node (ref "U14") (pin "8") (pinfunction "RS-_8") (pintype "passive"))
    )
    (net (code "26") (name "28Vout2") (class "Default")
      (node (ref "R172") (pin "2") (pinfunction "2_2") (pintype "passive"))
      (node (ref "R97") (pin "2") (pinfunction "2_2") (pintype "passive"))
      (node (ref "U18") (pin "8") (pinfunction "RS-_8") (pintype "passive"))
    )
    (net (code "27") (name "28Vout3") (class "Default")
      (node (ref "R171") (pin "2") (pinfunction "2_2") (pintype "passive"))
      (node (ref "R90") (pin "2") (pinfunction "2_2") (pintype "passive"))
      (node (ref "U15") (pin "8") (pinfunction "RS-_8") (pintype "passive"))
    )
    (net (code "28") (name "28Vout4") (class "Default")
      (node (ref "R173") (pin "2") (pinfunction "2_2") (pintype "passive"))
      (node (ref "R98") (pin "2") (pinfunction "2_2") (pintype "passive"))
      (node (ref "U19") (pin "8") (pinfunction "RS-_8") (pintype "passive"))
    )
    (net (code "29") (name "GND") (class "Default")
      (node (ref "C100") (pin "1") (pinfunction "1_1") (pintype "passive"))
      (node (ref "C101") (pin "1") (pinfunction "1_1") (pintype "passive"))
      (node (ref "C103") (pin "1") (pinfunction "1_1") (pintype "passive"))
      (node (ref "C104") (pin "1") (pinfunction "1_1") (pintype "passive"))
      (node (ref "C105") (pin "1") (pinfunction "1_1") (pintype "passive"))
      (node (ref "C106") (pin "1") (pinfunction "1_1") (pintype "passive"))
      (node (ref "C114") (pin "1") (pinfunction "1_1") (pintype "passive"))
      (node (ref "C12") (pin "1") (pinfunction "1_1") (pintype "passive"))
      (node (ref "C121") (pin "1") (pinfunction "1_1") (pintype "passive"))
      (node (ref "C128") (pin "1") (pinfunction "1_1") (pintype "passive"))
      (node (ref "C129") (pin "1") (pinfunction "1_1") (pintype "passive"))
      (node (ref "C132") (pin "1") (pinfunction "1_1") (pintype "passive"))
      (node (ref "C133") (pin "1") (pinfunction "1_1") (pintype "passive"))
      (node (ref "C134") (pin "1") (pinfunction "1_1") (pintype "passive"))
      (node (ref "C135") (pin "1") (pinfunction "1_1") (pintype "passive"))
      (node (ref "C141") (pin "1") (pinfunction "1_1") (pintype "passive"))
      (node (ref "C142") (pin "1") (pinfunction "1_1") (pintype "passive"))
      (node (ref "C15") (pin "1") (pinfunction "1_1") (pintype "passive"))
      (node (ref "C18") (pin "2") (pinfunction "2_2") (pintype "passive"))
      (node (ref "C181") (pin "1") (pinfunction "1_1") (pintype "passive"))
      (node (ref "C182") (pin "1") (pinfunction "1_1") (pintype "passive"))
      (node (ref "C183") (pin "1") (pinfunction "1_1") (pintype "passive"))
      (node (ref "C185") (pin "1") (pinfunction "1_1") (pintype "passive"))
      (node (ref "C19") (pin "2") (pinfunction "2_2") (pintype "passive"))
      (node (ref "C22") (pin "1") (pinfunction "1_1") (pintype "passive"))
      (node (ref "C23") (pin "1") (pinfunction "1_1") (pintype "passive"))
      (node (ref "C43") (pin "1") (pinfunction "1_1") (pintype "passive"))
      (node (ref "C52") (pin "1") (pinfunction "1_1") (pintype "passive"))
      (node (ref "C61") (pin "1") (pinfunction "1_1") (pintype "passive"))
      (node (ref "C64") (pin "2") (pinfunction "2_2") (pintype "passive"))
      (node (ref "C65") (pin "1") (pinfunction "1_1") (pintype "passive"))
      (node (ref "C66") (pin "1") (pinfunction "1_1") (pintype "passive"))
      (node (ref "C67") (pin "1") (pinfunction "1_1") (pintype "passive"))
      (node (ref "C68") (pin "1") (pinfunction "1_1") (pintype "passive"))
      (node (ref "C69") (pin "1") (pinfunction "1_1") (pintype "passive"))
      (node (ref "C70") (pin "1") (pinfunction "1_1") (pintype "passive"))
      (node (ref "C72") (pin "2") (pinfunction "2_2") (pintype "passive"))
      (node (ref "C73") (pin "1") (pinfunction "1_1") (pintype "passive"))
      (node (ref "C74") (pin "1") (pinfunction "1_1") (pintype "passive"))
      (node (ref "C75") (pin "2") (pinfunction "2_2") (pintype "passive"))
      (node (ref "C76") (pin "1") (pinfunction "1_1") (pintype "passive"))
      (node (ref "C77") (pin "1") (pinfunction "1_1") (pintype "passive"))
      (node (ref "C78") (pin "1") (pinfunction "1_1") (pintype "passive"))
      (node (ref "C79") (pin "1") (pinfunction "1_1") (pintype "passive"))
      (node (ref "C80") (pin "1") (pinfunction "1_1") (pintype "passive"))
      (node (ref "C82") (pin "1") (pinfunction "1_1") (pintype "passive"))
      (node (ref "C84") (pin "1") (pinfunction "1_1") (pintype "passive"))
      (node (ref "C85") (pin "1") (pinfunction "1_1") (pintype "passive"))
      (node (ref "C86") (pin "1") (pinfunction "1_1") (pintype "passive"))
      (node (ref "C87") (pin "2") (pinfunction "2_2") (pintype "passive"))
      (node (ref "C88") (pin "1") (pinfunction "1_1") (pintype "passive"))
      (node (ref "C89") (pin "1") (pinfunction "1_1") (pintype "passive"))
      (node (ref "C91") (pin "2") (pinfunction "2_2") (pintype "passive"))
      (node (ref "C92") (pin "1") (pinfunction "1_1") (pintype "passive"))
      (node (ref "C93") (pin "1") (pinfunction "1_1") (pintype "passive"))
      (node (ref "C94") (pin "1") (pinfunction "1_1") (pintype "passive"))
      (node (ref "C95") (pin "1") (pinfunction "1_1") (pintype "passive"))
      (node (ref "D1") (pin "1") (pinfunction "A_1") (pintype "passive"))
      (node (ref "Q1") (pin "2") (pinfunction "E_2") (pintype "passive"))
      (node (ref "Q5") (pin "2") (pinfunction "E_2") (pintype "passive"))
      (node (ref "Q6") (pin "2") (pinfunction "E_2") (pintype "passive"))
      (node (ref "Q7") (pin "2") (pinfunction "E_2") (pintype "passive"))
      (node (ref "R103") (pin "1") (pinfunction "1_1") (pintype "passive"))
      (node (ref "R162") (pin "1") (pinfunction "1_1") (pintype "passive"))
      (node (ref "R165") (pin "1") (pinfunction "1_1") (pintype "passive"))
      (node (ref "R169") (pin "2") (pinfunction "2_2") (pintype "passive"))
      (node (ref "R184") (pin "1") (pinfunction "1_1") (pintype "passive"))
      (node (ref "R82") (pin "2") (pinfunction "2_2") (pintype "passive"))
      (node (ref "R86") (pin "1") (pinfunction "1_1") (pintype "passive"))
      (node (ref "U10") (pin "1") (pinfunction "GND_1") (pintype "passive"))
      (node (ref "U11") (pin "1") (pinfunction "GND_1") (pintype "passive"))
      (node (ref "U14") (pin "4") (pinfunction "GND_4") (pintype "passive"))
      (node (ref "U15") (pin "4") (pinfunction "GND_4") (pintype "passive"))
      (node (ref "U18") (pin "4") (pinfunction "GND_4") (pintype "passive"))
      (node (ref "U19") (pin "4") (pinfunction "GND_4") (pintype "passive"))
      (node (ref "U25") (pin "3") (pinfunction "GND_3") (pintype "passive"))
      (node (ref "U25") (pin "6") (pinfunction "GND_6") (pintype "passive"))
      (node (ref "U27") (pin "2") (pinfunction "GND_2") (pintype "passive"))
      (node (ref "U27") (pin "4") (pinfunction "GND_4") (pintype "passive"))
      (node (ref "U28") (pin "2") (pinfunction "GND_2") (pintype "passive"))
      (node (ref "U28") (pin "4") (pinfunction "GND_4") (pintype "passive"))
      (node (ref "U29") (pin "2") (pinfunction "GND_2") (pintype "passive"))
      (node (ref "U29") (pin "4") (pinfunction "GND_4") (pintype "passive"))
      (node (ref "U30") (pin "2") (pinfunction "GND_2") (pintype "passive"))
      (node (ref "U30") (pin "4") (pinfunction "GND_4") (pintype "passive"))
      (node (ref "U9") (pin "4") (pinfunction "ON/OFF_4") (pintype "passive"))
      (node (ref "U9") (pin "5") (pinfunction "GND_5") (pintype "passive"))
      (node (ref "U9") (pin "6") (pinfunction "GND_6") (pintype "passive"))
      (node (ref "U9") (pin "7") (pinfunction "GND_7") (pintype "passive"))
      (node (ref "U9") (pin "8") (pinfunction "GND_8") (pintype "passive"))
      (node (ref "U9") (pin "9") (pinfunction "EP-GND_9") (pintype "passive"))
    )
    (net (code "30") (name "Net-(C82-Pad2)") (class "Default")
      (node (ref "C82") (pin "2") (pinfunction "2_2") (pintype "passive"))
      (node (ref "R83") (pin "2") (pinfunction "2_2") (pintype "passive"))
      (node (ref "R84") (pin "2") (pinfunction "2_2") (pintype "passive"))
      (node (ref "R86") (pin "2") (pinfunction "2_2") (pintype "passive"))
    )
    (net (code "31") (name "Net-(D1-K)") (class "Default")
      (node (ref "D1") (pin "2") (pinfunction "K_2") (pintype "passive"))
      (node (ref "L4") (pin "1") (pinfunction "1_1") (pintype "passive"))
      (node (ref "U9") (pin "2") (pinfunction "VOUT_2") (pintype "passive"))
    )
    (net (code "32") (name "Net-(Q1-B)") (class "Default")
      (node (ref "Q1") (pin "1") (pinfunction "B_1") (pintype "passive"))
      (node (ref "R103") (pin "2") (pinfunction "2_2") (pintype "passive"))
      (node (ref "R95") (pin "2") (pinfunction "2_2") (pintype "passive"))
    )
    (net (code "33") (name "Net-(Q1-C)") (class "Default")
      (node (ref "Q1") (pin "3") (pinfunction "C_3") (pintype "passive"))
      (node (ref "R85") (pin "1") (pinfunction "1_1") (pintype "passive"))
      (node (ref "R88") (pin "1") (pinfunction "1_1") (pintype "passive"))
    )
    (net (code "34") (name "Net-(Q5-B)") (class "Default")
      (node (ref "Q5") (pin "1") (pinfunction "B_1") (pintype "passive"))
      (node (ref "R160") (pin "2") (pinfunction "2_2") (pintype "passive"))
      (node (ref "R162") (pin "2") (pinfunction "2_2") (pintype "passive"))
    )
    (net (code "35") (name "Net-(Q5-C)") (class "Default")
      (node (ref "Q5") (pin "3") (pinfunction "C_3") (pintype "passive"))
      (node (ref "R104") (pin "1") (pinfunction "1_1") (pintype "passive"))
      (node (ref "R107") (pin "1") (pinfunction "1_1") (pintype "passive"))
    )
    (net (code "36") (name "Net-(Q6-B)") (class "Default")
      (node (ref "Q6") (pin "1") (pinfunction "B_1") (pintype "passive"))
      (node (ref "R183") (pin "2") (pinfunction "2_2") (pintype "passive"))
      (node (ref "R184") (pin "2") (pinfunction "2_2") (pintype "passive"))
    )
    (net (code "37") (name "Net-(Q6-C)") (class "Default")
      (node (ref "Q6") (pin "3") (pinfunction "C_3") (pintype "passive"))
      (node (ref "R181") (pin "1") (pinfunction "1_1") (pintype "passive"))
      (node (ref "R87") (pin "1") (pinfunction "1_1") (pintype "passive"))
    )
    (net (code "38") (name "Net-(Q7-B)") (class "Default")
      (node (ref "Q7") (pin "1") (pinfunction "B_1") (pintype "passive"))
      (node (ref "R161") (pin "2") (pinfunction "2_2") (pintype "passive"))
      (node (ref "R165") (pin "2") (pinfunction "2_2") (pintype "passive"))
    )
    (net (code "39") (name "Net-(Q7-C)") (class "Default")
      (node (ref "Q7") (pin "3") (pinfunction "C_3") (pintype "passive"))
      (node (ref "R105") (pin "1") (pinfunction "1_1") (pintype "passive"))
      (node (ref "R123") (pin "1") (pinfunction "1_1") (pintype "passive"))
    )
    (net (code "40") (name "Net-(R166-Pad2)") (class "Default")
      (node (ref "R166") (pin "2") (pinfunction "2_2") (pintype "passive"))
      (node (ref "R80") (pin "1") (pinfunction "1_1") (pintype "passive"))
    )
    (net (code "41") (name "Net-(R167-Pad1)") (class "Default")
      (node (ref "R167") (pin "1") (pinfunction "1_1") (pintype "passive"))
      (node (ref "R168") (pin "2") (pinfunction "2_2") (pintype "passive"))
    )
    (net (code "42") (name "Net-(U4-G)") (class "Default")
      (node (ref "R87") (pin "2") (pinfunction "2_2") (pintype "passive"))
      (node (ref "U4") (pin "1") (pinfunction "G_1") (pintype "passive"))
    )
    (net (code "43") (name "Net-(U4-S)") (class "Default")
      (node (ref "C141") (pin "2") (pinfunction "2_2") (pintype "passive"))
      (node (ref "C18") (pin "1") (pinfunction "1_1") (pintype "passive"))
      (node (ref "FB18") (pin "1") (pinfunction "1_1") (pintype "passive"))
      (node (ref "U4") (pin "2") (pinfunction "S_2") (pintype "passive"))
    )
    (net (code "44") (name "Net-(U9-FB{slash}ADJ)") (class "Default")
      (node (ref "R166") (pin "1") (pinfunction "1_1") (pintype "passive"))
      (node (ref "R82") (pin "1") (pinfunction "1_1") (pintype "passive"))
      (node (ref "U9") (pin "3") (pinfunction "FB/ADJ_3") (pintype "passive"))
    )
    (net (code "45") (name "Net-(U12-G)") (class "Default")
      (node (ref "R88") (pin "2") (pinfunction "2_2") (pintype "passive"))
      (node (ref "U12") (pin "1") (pinfunction "G_1") (pintype "passive"))
    )
    (net (code "46") (name "Net-(U12-S)") (class "Default")
      (node (ref "C15") (pin "2") (pinfunction "2_2") (pintype "passive"))
      (node (ref "C19") (pin "1") (pinfunction "1_1") (pintype "passive"))
      (node (ref "FB15") (pin "1") (pinfunction "1_1") (pintype "passive"))
      (node (ref "U12") (pin "2") (pinfunction "S_2") (pintype "passive"))
    )
    (net (code "47") (name "Net-(U14-OUT)") (class "Default")
      (node (ref "R93") (pin "1") (pinfunction "1_1") (pintype "passive"))
      (node (ref "U14") (pin "5") (pinfunction "OUT_5") (pintype "passive"))
    )
    (net (code "48") (name "Net-(U15-OUT)") (class "Default")
      (node (ref "R94") (pin "1") (pinfunction "1_1") (pintype "passive"))
      (node (ref "U15") (pin "5") (pinfunction "OUT_5") (pintype "passive"))
    )
    (net (code "49") (name "Net-(U18-OUT)") (class "Default")
      (node (ref "R100") (pin "1") (pinfunction "1_1") (pintype "passive"))
      (node (ref "U18") (pin "5") (pinfunction "OUT_5") (pintype "passive"))
    )
    (net (code "50") (name "Net-(U19-OUT)") (class "Default")
      (node (ref "R101") (pin "1") (pinfunction "1_1") (pintype "passive"))
      (node (ref "U19") (pin "5") (pinfunction "OUT_5") (pintype "passive"))
    )
    (net (code "51") (name "Net-(U20-G)") (class "Default")
      (node (ref "R107") (pin "2") (pinfunction "2_2") (pintype "passive"))
      (node (ref "U20") (pin "1") (pinfunction "G_1") (pintype "passive"))
    )
    (net (code "52") (name "Net-(U20-S)") (class "Default")
      (node (ref "C61") (pin "2") (pinfunction "2_2") (pintype "passive"))
      (node (ref "C75") (pin "1") (pinfunction "1_1") (pintype "passive"))
      (node (ref "FB16") (pin "1") (pinfunction "1_1") (pintype "passive"))
      (node (ref "U20") (pin "2") (pinfunction "S_2") (pintype "passive"))
    )
    (net (code "53") (name "Net-(U21-G)") (class "Default")
      (node (ref "R123") (pin "2") (pinfunction "2_2") (pintype "passive"))
      (node (ref "U21") (pin "1") (pinfunction "G_1") (pintype "passive"))
    )
    (net (code "54") (name "Net-(U21-S)") (class "Default")
      (node (ref "C74") (pin "2") (pinfunction "2_2") (pintype "passive"))
      (node (ref "C91") (pin "1") (pinfunction "1_1") (pintype "passive"))
      (node (ref "FB17") (pin "1") (pinfunction "1_1") (pintype "passive"))
      (node (ref "U21") (pin "2") (pinfunction "S_2") (pintype "passive"))
    )
    (net (code "55") (name "Net-(U25-EN)") (class "Default")
      (node (ref "R231") (pin "1") (pinfunction "1_1") (pintype "passive"))
      (node (ref "U25") (pin "5") (pinfunction "EN_5") (pintype "passive"))
    )
    (net (code "56") (name "Net-(U25-NR{slash}FB)") (class "Default")
      (node (ref "C184") (pin "1") (pinfunction "1_1") (pintype "passive"))
      (node (ref "R168") (pin "1") (pinfunction "1_1") (pintype "passive"))
      (node (ref "R169") (pin "1") (pinfunction "1_1") (pintype "passive"))
      (node (ref "U25") (pin "4") (pinfunction "NR/FB_4") (pintype "passive"))
    )
    (net (code "57") (name "unconnected-(U14-NC-Pad3)") (class "Default")
      (node (ref "U14") (pin "3") (pinfunction "NC_3") (pintype "passive"))
    )
    (net (code "58") (name "unconnected-(U14-NC-Pad6)") (class "Default")
      (node (ref "U14") (pin "6") (pinfunction "NC_6") (pintype "passive"))
    )
    (net (code "59") (name "unconnected-(U14-NC-Pad7)") (class "Default")
      (node (ref "U14") (pin "7") (pinfunction "NC_7") (pintype "passive"))
    )
    (net (code "60") (name "unconnected-(U15-NC-Pad3)") (class "Default")
      (node (ref "U15") (pin "3") (pinfunction "NC_3") (pintype "passive"))
    )
    (net (code "61") (name "unconnected-(U15-NC-Pad6)") (class "Default")
      (node (ref "U15") (pin "6") (pinfunction "NC_6") (pintype "passive"))
    )
    (net (code "62") (name "unconnected-(U15-NC-Pad7)") (class "Default")
      (node (ref "U15") (pin "7") (pinfunction "NC_7") (pintype "passive"))
    )
    (net (code "63") (name "unconnected-(U18-NC-Pad3)") (class "Default")
      (node (ref "U18") (pin "3") (pinfunction "NC_3") (pintype "passive"))
    )
    (net (code "64") (name "unconnected-(U18-NC-Pad6)") (class "Default")
      (node (ref "U18") (pin "6") (pinfunction "NC_6") (pintype "passive"))
    )
    (net (code "65") (name "unconnected-(U18-NC-Pad7)") (class "Default")
      (node (ref "U18") (pin "7") (pinfunction "NC_7") (pintype "passive"))
    )
    (net (code "66") (name "unconnected-(U19-NC-Pad3)") (class "Default")
      (node (ref "U19") (pin "3") (pinfunction "NC_3") (pintype "passive"))
    )
    (net (code "67") (name "unconnected-(U19-NC-Pad6)") (class "Default")
      (node (ref "U19") (pin "6") (pinfunction "NC_6") (pintype "passive"))
    )
    (net (code "68") (name "unconnected-(U19-NC-Pad7)") (class "Default")
      (node (ref "U19") (pin "7") (pinfunction "NC_7") (pintype "passive"))
    )
  )
)
